# 8_imu_debug_conn.net
KiCad netlist of a schematic drawn in Altium Designer
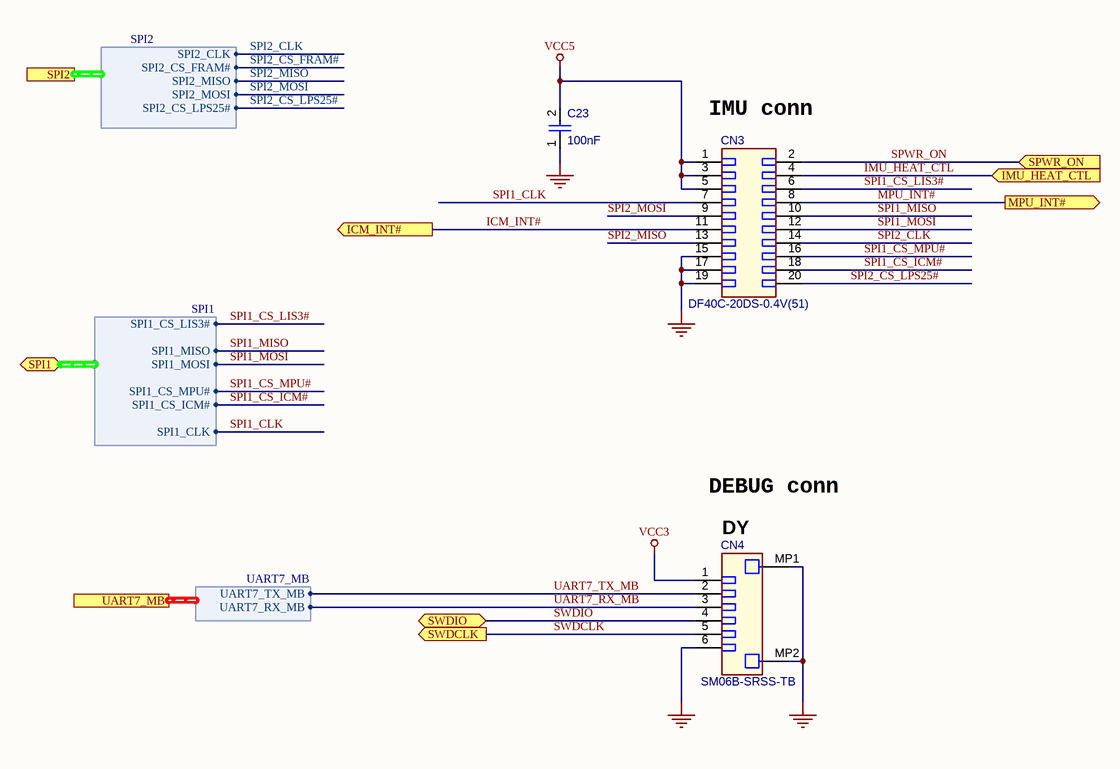
[diagram p0: 8_imu&debug_conn.SchDoc]

(export (version "E")
  (design (tool "Eeschema 10.0.6"))
  (components
    (comp (ref "C23")
      (value "100nF")
      (footprint "CAPC0402(1005)60_L")
      (description "Chip Capacitor, 100nF +/-20%, 10V, 0402, Thickness 0.6 mm")
      (fields (field (name "TOLERANCE") "20%") (field (name "Comment") "Capacitor 100nF +/-20% 10V 0402"))
      (libsource (lib "<Company> Server") (part "CAP-NP-2"))
    )
    (comp (ref "CN3")
      (value "DF40C-20DS-0.4V(51)")
      (footprint "HIRO-DF40C-20DS-0.4V(51)_V")
      (description "Receptacle Connector, 30 V, 0.3 A, -35 to 85 degC, RoHS, Tape and Reel")
      (libsource (lib "<Company> Server") (part "CMP-00114-7"))
    )
    (comp (ref "CN4")
      (value "SM06B-SRSS-TB")
      (footprint "JST-SM06B-SRSS-TB_V")
      (description "Male Header, Pitch 1 mm, 1 x 6 Position, Height 2.95 mm, -25 to 85 degC, RoHS, Tape and Reel")
      (libsource (lib "<Company> Server") (part "CMP-00143-5"))
    )
  )
  (nets
    (net (code "4") (name "/ICM_INT#") (class "Default")
      (node (ref "CN3") (pin "11") (pinfunction "11_11") (pintype "passive"))
    )
    (net (code "5") (name "/IMU_HEAT_CTL") (class "Default")
      (node (ref "CN3") (pin "4") (pinfunction "4_4") (pintype "passive"))
    )
    (net (code "6") (name "/MPU_INT#") (class "Default")
      (node (ref "CN3") (pin "8") (pinfunction "8_8") (pintype "passive"))
    )
    (net (code "7") (name "/SPI1_CLK") (class "Default")
      (node (ref "CN3") (pin "7") (pinfunction "7_7") (pintype "passive"))
    )
    (net (code "8") (name "/SPI1_CS_ICM#") (class "Default")
      (node (ref "CN3") (pin "18") (pinfunction "18_18") (pintype "passive"))
    )
    (net (code "9") (name "/SPI1_CS_LIS3#") (class "Default")
      (node (ref "CN3") (pin "6") (pinfunction "6_6") (pintype "passive"))
    )
    (net (code "10") (name "/SPI1_CS_MPU#") (class "Default")
      (node (ref "CN3") (pin "16") (pinfunction "16_16") (pintype "passive"))
    )
    (net (code "11") (name "/SPI1_MISO") (class "Default")
      (node (ref "CN3") (pin "10") (pinfunction "10_10") (pintype "passive"))
    )
    (net (code "12") (name "/SPI1_MOSI") (class "Default")
      (node (ref "CN3") (pin "12") (pinfunction "12_12") (pintype "passive"))
    )
    (net (code "13") (name "/SPI2_CLK") (class "Default")
      (node (ref "CN3") (pin "14") (pinfunction "14_14") (pintype "passive"))
    )
    (net (code "15") (name "/SPI2_CS_LPS25#") (class "Default")
      (node (ref "CN3") (pin "20") (pinfunction "20_20") (pintype "passive"))
    )
    (net (code "16") (name "/SPI2_MISO") (class "Default")
      (node (ref "CN3") (pin "13") (pinfunction "13_13") (pintype "passive"))
    )
    (net (code "17") (name "/SPI2_MOSI") (class "Default")
      (node (ref "CN3") (pin "9") (pinfunction "9_9") (pintype "passive"))
    )
    (net (code "18") (name "/SPWR_ON") (class "Default")
      (node (ref "CN3") (pin "2") (pinfunction "2_2") (pintype "passive"))
    )
    (net (code "19") (name "/SWDCLK") (class "Default")
      (node (ref "CN4") (pin "5") (pinfunction "5_5") (pintype "passive"))
    )
    (net (code "20") (name "/SWDIO") (class "Default")
      (node (ref "CN4") (pin "4") (pinfunction "4_4") (pintype "passive"))
    )
    (net (code "21") (name "/UART7_RX_MB") (class "Default")
      (node (ref "CN4") (pin "3") (pinfunction "3_3") (pintype "passive"))
    )
    (net (code "22") (name "/UART7_TX_MB") (class "Default")
      (node (ref "CN4") (pin "2") (pinfunction "2_2") (pintype "passive"))
    )
    (net (code "26") (name "GND") (class "Default")
      (node (ref "C23") (pin "1") (pinfunction "1_1") (pintype "passive"))
      (node (ref "CN3") (pin "15") (pinfunction "15_15") (pintype "passive"))
      (node (ref "CN3") (pin "17") (pinfunction "17_17") (pintype "passive"))
      (node (ref "CN3") (pin "19") (pinfunction "19_19") (pintype "passive"))
      (node (ref "CN4") (pin "6") (pinfunction "6_6") (pintype "passive"))
      (node (ref "CN4") (pin "MP1") (pinfunction "MP1_MP1") (pintype "passive"))
      (node (ref "CN4") (pin "MP2") (pinfunction "MP2_MP2") (pintype "passive"))
    )
    (net (code "27") (name "VCC3") (class "Default")
      (node (ref "CN4") (pin "1") (pinfunction "1_1") (pintype "passive"))
    )
    (net (code "28") (name "VCC5") (class "Default")
      (node (ref "C23") (pin "2") (pinfunction "2_2") (pintype "passive"))
      (node (ref "CN3") (pin "1") (pinfunction "1_1") (pintype "passive"))
      (node (ref "CN3") (pin "3") (pinfunction "3_3") (pintype "passive"))
      (node (ref "CN3") (pin "5") (pinfunction "5_5") (pintype "passive"))
    )
  )
)
